# BALPGA.net
KiCad netlist of a schematic drawn in EAGLE
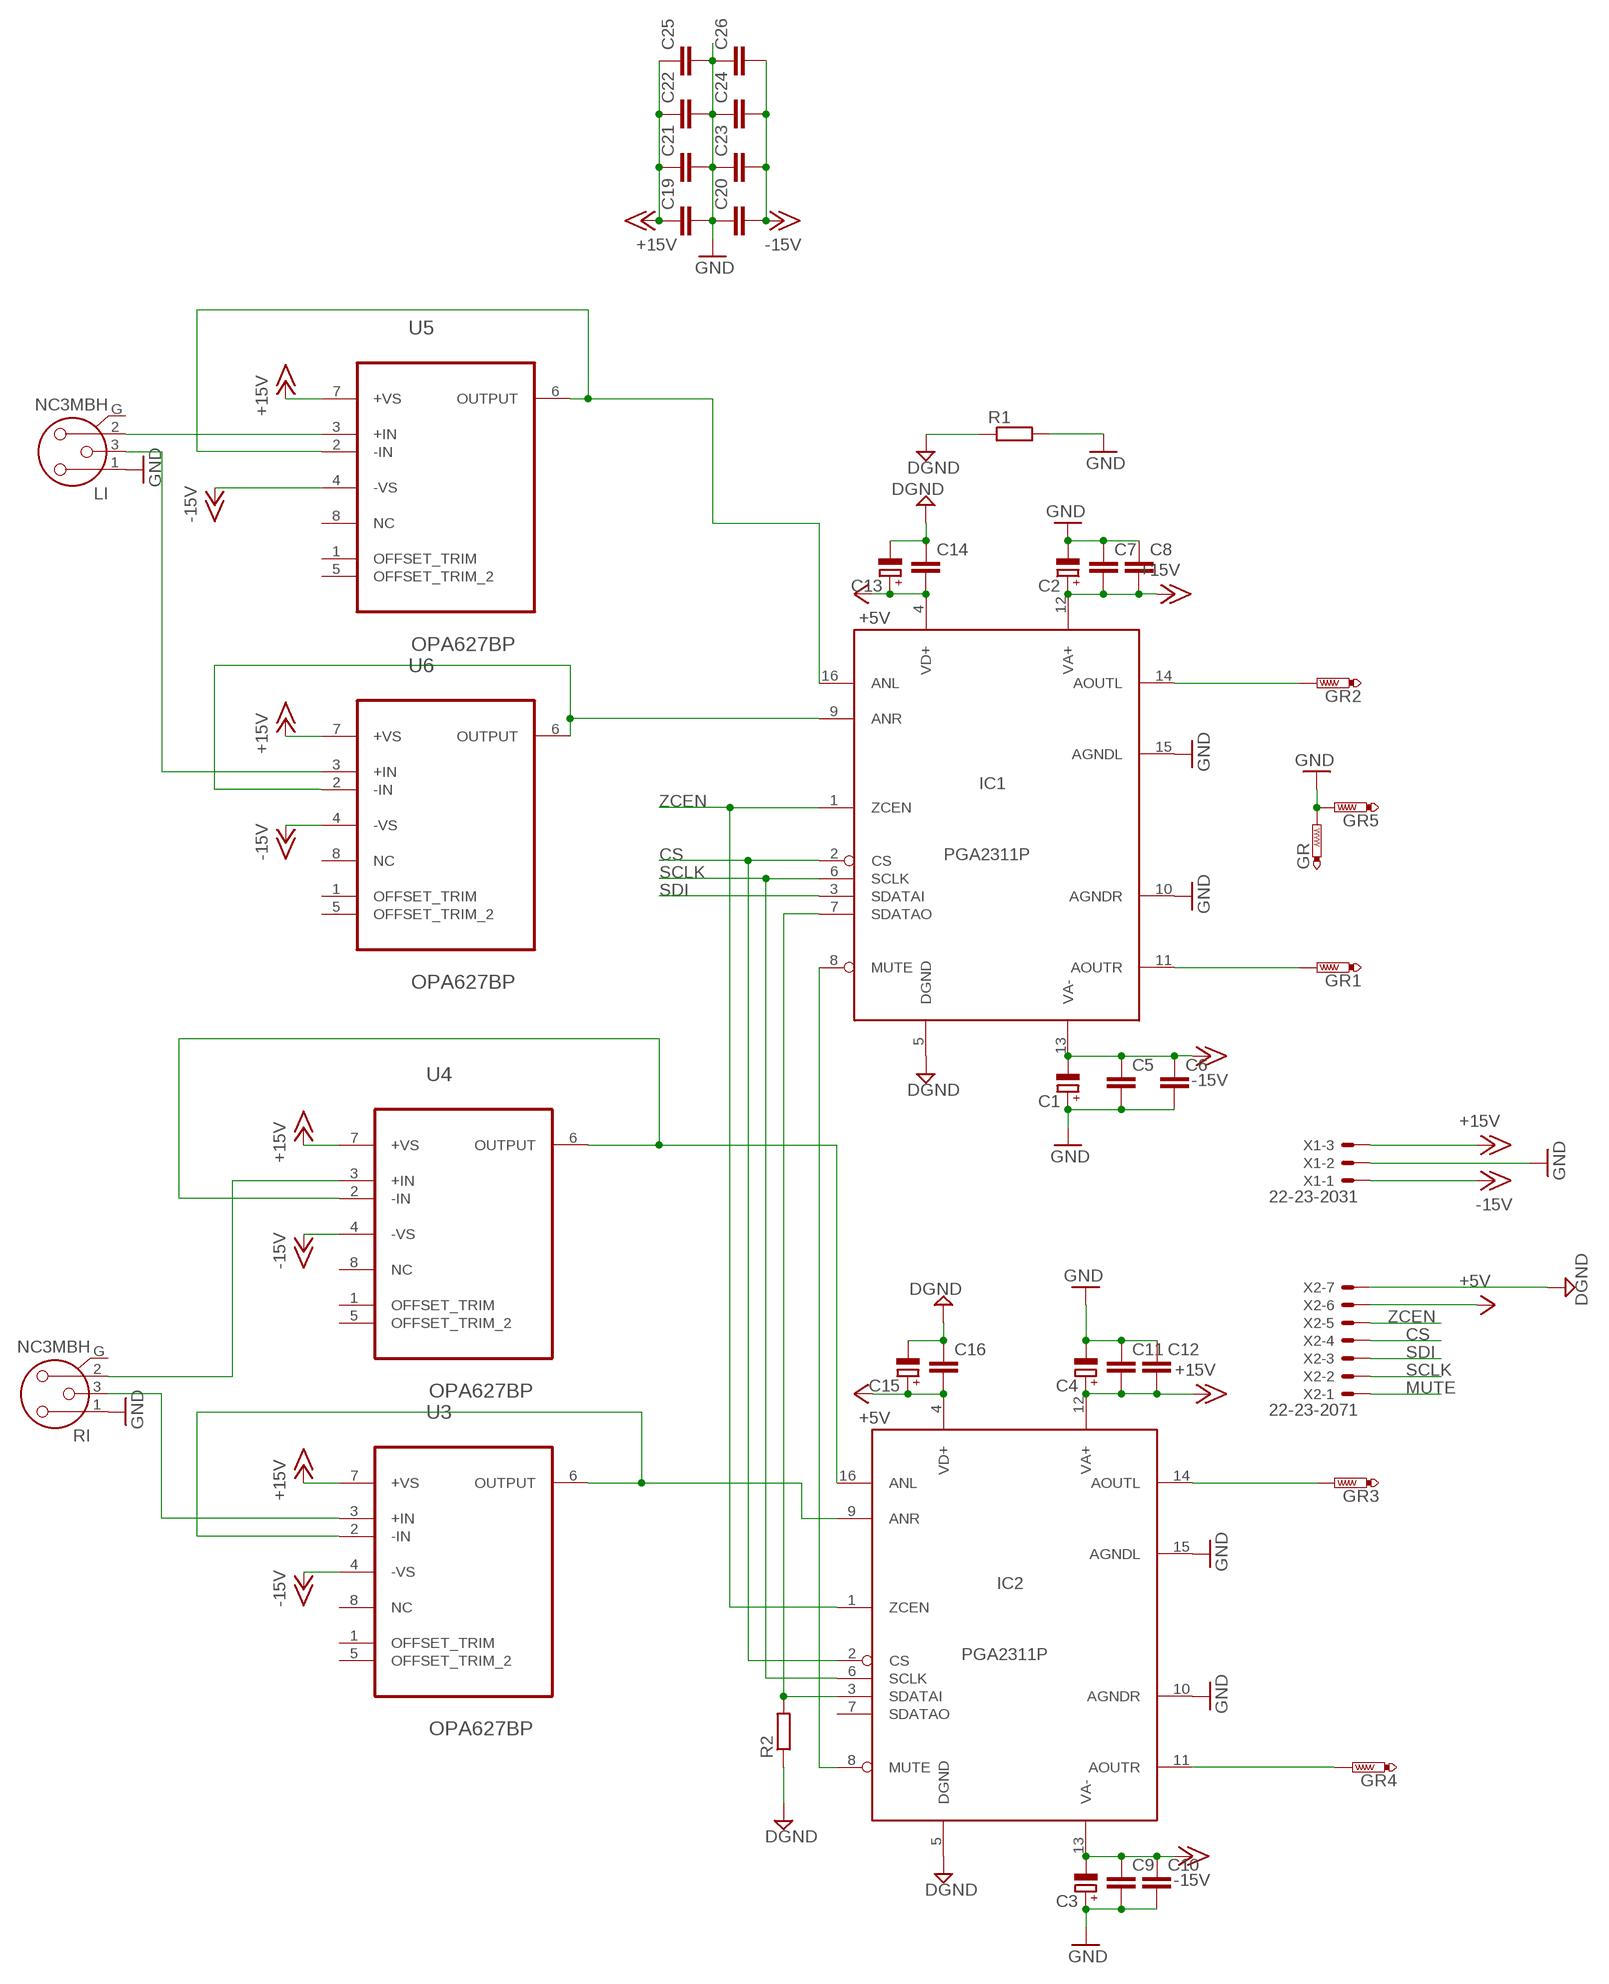
[diagram p0: schematic, sheet 1]

(export (version "E")
  (design (tool "Eeschema 10.0.6"))
  (components
    (comp (ref "C1")
      (value "CPOL-EUSMCD")
      (footprint "eagle-import:SMC_D")
      (libsource (lib "eagle-import") (part "CPOL-EUSMCD"))
    )
    (comp (ref "C2")
      (value "CPOL-EUSMCD")
      (footprint "eagle-import:SMC_D")
      (libsource (lib "eagle-import") (part "CPOL-EUSMCD"))
    )
    (comp (ref "C3")
      (value "CPOL-EUSMCD")
      (footprint "eagle-import:SMC_D")
      (libsource (lib "eagle-import") (part "CPOL-EUSMCD"))
    )
    (comp (ref "C4")
      (value "CPOL-EUSMCD")
      (footprint "eagle-import:SMC_D")
      (libsource (lib "eagle-import") (part "CPOL-EUSMCD"))
    )
    (comp (ref "C5")
      (value "C-EUC1206")
      (footprint "eagle-import:C1206")
      (libsource (lib "eagle-import") (part "C-EUC1206"))
    )
    (comp (ref "C6")
      (value "C-EUC1206")
      (footprint "eagle-import:C1206")
      (libsource (lib "eagle-import") (part "C-EUC1206"))
    )
    (comp (ref "C7")
      (value "C-EUC1206")
      (footprint "eagle-import:C1206")
      (libsource (lib "eagle-import") (part "C-EUC1206"))
    )
    (comp (ref "C8")
      (value "C-EUC1206")
      (footprint "eagle-import:C1206")
      (libsource (lib "eagle-import") (part "C-EUC1206"))
    )
    (comp (ref "C9")
      (value "C-EUC1206")
      (footprint "eagle-import:C1206")
      (libsource (lib "eagle-import") (part "C-EUC1206"))
    )
    (comp (ref "C10")
      (value "C-EUC1206")
      (footprint "eagle-import:C1206")
      (libsource (lib "eagle-import") (part "C-EUC1206"))
    )
    (comp (ref "C11")
      (value "C-EUC1206")
      (footprint "eagle-import:C1206")
      (libsource (lib "eagle-import") (part "C-EUC1206"))
    )
    (comp (ref "C12")
      (value "C-EUC1206")
      (footprint "eagle-import:C1206")
      (libsource (lib "eagle-import") (part "C-EUC1206"))
    )
    (comp (ref "C13")
      (value "CPOL-EUSMCD")
      (footprint "eagle-import:SMC_D")
      (libsource (lib "eagle-import") (part "CPOL-EUSMCD"))
    )
    (comp (ref "C14")
      (value "C-EUC1206")
      (footprint "eagle-import:C1206")
      (libsource (lib "eagle-import") (part "C-EUC1206"))
    )
    (comp (ref "C15")
      (value "CPOL-EUSMCD")
      (footprint "eagle-import:SMC_D")
      (libsource (lib "eagle-import") (part "CPOL-EUSMCD"))
    )
    (comp (ref "C16")
      (value "C-EUC1206")
      (footprint "eagle-import:C1206")
      (libsource (lib "eagle-import") (part "C-EUC1206"))
    )
    (comp (ref "C19")
      (value "C-EUC1206")
      (footprint "eagle-import:C1206")
      (libsource (lib "eagle-import") (part "C-EUC1206"))
    )
    (comp (ref "C20")
      (value "C-EUC1206")
      (footprint "eagle-import:C1206")
      (libsource (lib "eagle-import") (part "C-EUC1206"))
    )
    (comp (ref "C21")
      (value "C-EUC1206")
      (footprint "eagle-import:C1206")
      (libsource (lib "eagle-import") (part "C-EUC1206"))
    )
    (comp (ref "C22")
      (value "C-EUC1206")
      (footprint "eagle-import:C1206")
      (libsource (lib "eagle-import") (part "C-EUC1206"))
    )
    (comp (ref "C23")
      (value "C-EUC1206")
      (footprint "eagle-import:C1206")
      (libsource (lib "eagle-import") (part "C-EUC1206"))
    )
    (comp (ref "C24")
      (value "C-EUC1206")
      (footprint "eagle-import:C1206")
      (libsource (lib "eagle-import") (part "C-EUC1206"))
    )
    (comp (ref "C25")
      (value "C-EUC1206")
      (footprint "eagle-import:C1206")
      (libsource (lib "eagle-import") (part "C-EUC1206"))
    )
    (comp (ref "C26")
      (value "C-EUC1206")
      (footprint "eagle-import:C1206")
      (libsource (lib "eagle-import") (part "C-EUC1206"))
    )
    (comp (ref "GR")
      (value "PTR1PAD1-17")
      (footprint "eagle-import:P1-17")
      (libsource (lib "eagle-import") (part "PTR1PAD1-17"))
    )
    (comp (ref "GR1")
      (value "PTR1PAD1-17")
      (footprint "eagle-import:P1-17")
      (libsource (lib "eagle-import") (part "PTR1PAD1-17"))
    )
    (comp (ref "GR2")
      (value "PTR1PAD1-17")
      (footprint "eagle-import:P1-17")
      (libsource (lib "eagle-import") (part "PTR1PAD1-17"))
    )
    (comp (ref "GR3")
      (value "PTR1PAD1-17")
      (footprint "eagle-import:P1-17")
      (libsource (lib "eagle-import") (part "PTR1PAD1-17"))
    )
    (comp (ref "GR4")
      (value "PTR1PAD1-17")
      (footprint "eagle-import:P1-17")
      (libsource (lib "eagle-import") (part "PTR1PAD1-17"))
    )
    (comp (ref "GR5")
      (value "PTR1PAD1-17")
      (footprint "eagle-import:P1-17")
      (libsource (lib "eagle-import") (part "PTR1PAD1-17"))
    )
    (comp (ref "IC1")
      (value "PGA2311P")
      (footprint "eagle-import:DIL16")
      (libsource (lib "eagle-import") (part "PGA2311P"))
    )
    (comp (ref "IC2")
      (value "PGA2311P")
      (footprint "eagle-import:DIL16")
      (libsource (lib "eagle-import") (part "PGA2311P"))
    )
    (comp (ref "LI")
      (value "NC3MBH")
      (footprint "eagle-import:NC3MBH")
      (fields (field (name "MF") "NEUTRIK"))
      (libsource (lib "eagle-import") (part "NC3MBH"))
    )
    (comp (ref "R1")
      (value "R-EU_0207/10")
      (footprint "eagle-import:0207_10")
      (libsource (lib "eagle-import") (part "resistor_R-EU_0207/10"))
    )
    (comp (ref "R2")
      (value "R-EU_R1206")
      (footprint "eagle-import:R1206")
      (libsource (lib "eagle-import") (part "R-EU_R1206"))
    )
    (comp (ref "RI")
      (value "NC3MBH")
      (footprint "eagle-import:NC3MBH")
      (fields (field (name "MF") "NEUTRIK"))
      (libsource (lib "eagle-import") (part "NC3MBH"))
    )
    (comp (ref "U3")
      (value "OPA627BP")
      (footprint "eagle-import:DIL08")
      (libsource (lib "eagle-import") (part "OPA627BP"))
    )
    (comp (ref "U4")
      (value "OPA627BP")
      (footprint "eagle-import:DIL08")
      (libsource (lib "eagle-import") (part "OPA627BP"))
    )
    (comp (ref "U5")
      (value "OPA627BP")
      (footprint "eagle-import:DIL08")
      (libsource (lib "eagle-import") (part "OPA627BP"))
    )
    (comp (ref "U6")
      (value "OPA627BP")
      (footprint "eagle-import:DIL08")
      (libsource (lib "eagle-import") (part "OPA627BP"))
    )
    (comp (ref "X1")
      (value "22-23-2031")
      (footprint "eagle-import:22-23-2031")
      (fields (field (name "MF") "MOLEX"))
      (libsource (lib "eagle-import") (part "22-23-2031"))
    )
    (comp (ref "X2")
      (value "22-23-2071")
      (footprint "eagle-import:22-23-2071")
      (fields (field (name "MF") "MOLEX"))
      (libsource (lib "eagle-import") (part "22-23-2071"))
    )
  )
  (nets
    (net (code "1") (name "+5V") (class "Default")
      (node (ref "C13") (pin "+") (pinfunction "+_+") (pintype "passive"))
      (node (ref "C14") (pin "2") (pinfunction "2_2") (pintype "passive"))
      (node (ref "C15") (pin "+") (pinfunction "+_+") (pintype "passive"))
      (node (ref "C16") (pin "2") (pinfunction "2_2") (pintype "passive"))
      (node (ref "IC1") (pin "4") (pinfunction "VD+_4") (pintype "power_in"))
      (node (ref "IC2") (pin "4") (pinfunction "VD+_4") (pintype "power_in"))
      (node (ref "X2") (pin "6") (pinfunction "S_6") (pintype "passive"))
    )
    (net (code "2") (name "+15V") (class "Default")
      (node (ref "C11") (pin "2") (pinfunction "2_2") (pintype "passive"))
      (node (ref "C12") (pin "2") (pinfunction "2_2") (pintype "passive"))
      (node (ref "C19") (pin "1") (pinfunction "1_1") (pintype "passive"))
      (node (ref "C2") (pin "+") (pinfunction "+_+") (pintype "passive"))
      (node (ref "C21") (pin "1") (pinfunction "1_1") (pintype "passive"))
      (node (ref "C22") (pin "1") (pinfunction "1_1") (pintype "passive"))
      (node (ref "C25") (pin "1") (pinfunction "1_1") (pintype "passive"))
      (node (ref "C4") (pin "+") (pinfunction "+_+") (pintype "passive"))
      (node (ref "C7") (pin "2") (pinfunction "2_2") (pintype "passive"))
      (node (ref "C8") (pin "2") (pinfunction "2_2") (pintype "passive"))
      (node (ref "IC1") (pin "12") (pinfunction "VA+_12") (pintype "power_in"))
      (node (ref "IC2") (pin "12") (pinfunction "VA+_12") (pintype "power_in"))
      (node (ref "U3") (pin "7") (pinfunction "+VS_7") (pintype "power_in"))
      (node (ref "U4") (pin "7") (pinfunction "+VS_7") (pintype "power_in"))
      (node (ref "U5") (pin "7") (pinfunction "+VS_7") (pintype "power_in"))
      (node (ref "U6") (pin "7") (pinfunction "+VS_7") (pintype "power_in"))
      (node (ref "X1") (pin "3") (pinfunction "S_3") (pintype "passive"))
    )
    (net (code "3") (name "-15V") (class "Default")
      (node (ref "C1") (pin "-") (pinfunction "-_-") (pintype "passive"))
      (node (ref "C10") (pin "1") (pinfunction "1_1") (pintype "passive"))
      (node (ref "C20") (pin "2") (pinfunction "2_2") (pintype "passive"))
      (node (ref "C23") (pin "2") (pinfunction "2_2") (pintype "passive"))
      (node (ref "C24") (pin "2") (pinfunction "2_2") (pintype "passive"))
      (node (ref "C26") (pin "2") (pinfunction "2_2") (pintype "passive"))
      (node (ref "C3") (pin "-") (pinfunction "-_-") (pintype "passive"))
      (node (ref "C5") (pin "1") (pinfunction "1_1") (pintype "passive"))
      (node (ref "C6") (pin "1") (pinfunction "1_1") (pintype "passive"))
      (node (ref "C9") (pin "1") (pinfunction "1_1") (pintype "passive"))
      (node (ref "IC1") (pin "13") (pinfunction "VA-_13") (pintype "power_in"))
      (node (ref "IC2") (pin "13") (pinfunction "VA-_13") (pintype "power_in"))
      (node (ref "U3") (pin "4") (pinfunction "-VS_4") (pintype "power_in"))
      (node (ref "U4") (pin "4") (pinfunction "-VS_4") (pintype "power_in"))
      (node (ref "U5") (pin "4") (pinfunction "-VS_4") (pintype "power_in"))
      (node (ref "U6") (pin "4") (pinfunction "-VS_4") (pintype "power_in"))
      (node (ref "X1") (pin "1") (pinfunction "S_1") (pintype "passive"))
    )
    (net (code "4") (name "/CS") (class "Default")
      (node (ref "IC1") (pin "2") (pinfunction "CS_2") (pintype "input"))
      (node (ref "IC2") (pin "2") (pinfunction "CS_2") (pintype "input"))
      (node (ref "X2") (pin "4") (pinfunction "S_4") (pintype "passive"))
    )
    (net (code "5") (name "/MUTE") (class "Default")
      (node (ref "IC1") (pin "8") (pinfunction "MUTE_8") (pintype "input"))
      (node (ref "IC2") (pin "8") (pinfunction "MUTE_8") (pintype "input"))
      (node (ref "X2") (pin "1") (pinfunction "S_1") (pintype "passive"))
    )
    (net (code "6") (name "/SCLK") (class "Default")
      (node (ref "IC1") (pin "6") (pinfunction "SCLK_6") (pintype "input"))
      (node (ref "IC2") (pin "6") (pinfunction "SCLK_6") (pintype "input"))
      (node (ref "X2") (pin "2") (pinfunction "S_2") (pintype "passive"))
    )
    (net (code "7") (name "/SDI") (class "Default")
      (node (ref "IC1") (pin "3") (pinfunction "SDATAI_3") (pintype "input"))
      (node (ref "X2") (pin "3") (pinfunction "S_3") (pintype "passive"))
    )
    (net (code "8") (name "/ZCEN") (class "Default")
      (node (ref "IC1") (pin "1") (pinfunction "ZCEN_1") (pintype "input"))
      (node (ref "IC2") (pin "1") (pinfunction "ZCEN_1") (pintype "input"))
      (node (ref "X2") (pin "5") (pinfunction "S_5") (pintype "passive"))
    )
    (net (code "9") (name "DGND") (class "Default")
      (node (ref "C13") (pin "-") (pinfunction "-_-") (pintype "passive"))
      (node (ref "C14") (pin "1") (pinfunction "1_1") (pintype "passive"))
      (node (ref "C15") (pin "-") (pinfunction "-_-") (pintype "passive"))
      (node (ref "C16") (pin "1") (pinfunction "1_1") (pintype "passive"))
      (node (ref "IC1") (pin "5") (pinfunction "DGND_5") (pintype "power_in"))
      (node (ref "IC2") (pin "5") (pinfunction "DGND_5") (pintype "power_in"))
      (node (ref "R1") (pin "1") (pinfunction "1_1") (pintype "passive"))
      (node (ref "R2") (pin "1") (pinfunction "1_1") (pintype "passive"))
      (node (ref "X2") (pin "7") (pinfunction "S_7") (pintype "passive"))
    )
    (net (code "10") (name "GND") (class "Default")
      (node (ref "C1") (pin "+") (pinfunction "+_+") (pintype "passive"))
      (node (ref "C10") (pin "2") (pinfunction "2_2") (pintype "passive"))
      (node (ref "C11") (pin "1") (pinfunction "1_1") (pintype "passive"))
      (node (ref "C12") (pin "1") (pinfunction "1_1") (pintype "passive"))
      (node (ref "C19") (pin "2") (pinfunction "2_2") (pintype "passive"))
      (node (ref "C2") (pin "-") (pinfunction "-_-") (pintype "passive"))
      (node (ref "C20") (pin "1") (pinfunction "1_1") (pintype "passive"))
      (node (ref "C21") (pin "2") (pinfunction "2_2") (pintype "passive"))
      (node (ref "C22") (pin "2") (pinfunction "2_2") (pintype "passive"))
      (node (ref "C23") (pin "1") (pinfunction "1_1") (pintype "passive"))
      (node (ref "C24") (pin "1") (pinfunction "1_1") (pintype "passive"))
      (node (ref "C25") (pin "2") (pinfunction "2_2") (pintype "passive"))
      (node (ref "C26") (pin "1") (pinfunction "1_1") (pintype "passive"))
      (node (ref "C3") (pin "+") (pinfunction "+_+") (pintype "passive"))
      (node (ref "C4") (pin "-") (pinfunction "-_-") (pintype "passive"))
      (node (ref "C5") (pin "2") (pinfunction "2_2") (pintype "passive"))
      (node (ref "C6") (pin "2") (pinfunction "2_2") (pintype "passive"))
      (node (ref "C7") (pin "1") (pinfunction "1_1") (pintype "passive"))
      (node (ref "C8") (pin "1") (pinfunction "1_1") (pintype "passive"))
      (node (ref "C9") (pin "2") (pinfunction "2_2") (pintype "passive"))
      (node (ref "GR") (pin "TP") (pinfunction "TP_TP") (pintype "input"))
      (node (ref "GR5") (pin "TP") (pinfunction "TP_TP") (pintype "input"))
      (node (ref "IC1") (pin "10") (pinfunction "AGNDR_10") (pintype "power_in"))
      (node (ref "IC1") (pin "15") (pinfunction "AGNDL_15") (pintype "power_in"))
      (node (ref "IC2") (pin "10") (pinfunction "AGNDR_10") (pintype "power_in"))
      (node (ref "IC2") (pin "15") (pinfunction "AGNDL_15") (pintype "power_in"))
      (node (ref "LI") (pin "1") (pinfunction "1_1") (pintype "passive"))
      (node (ref "R1") (pin "2") (pinfunction "2_2") (pintype "passive"))
      (node (ref "RI") (pin "1") (pinfunction "1_1") (pintype "passive"))
      (node (ref "X1") (pin "2") (pinfunction "S_2") (pintype "passive"))
    )
    (net (code "11") (name "Net-(IC1-ANL)") (class "Default")
      (node (ref "IC1") (pin "16") (pinfunction "ANL_16") (pintype "input"))
      (node (ref "U5") (pin "2") (pinfunction "-IN_2") (pintype "input"))
      (node (ref "U5") (pin "6") (pinfunction "OUTPUT_6") (pintype "output"))
    )
    (net (code "12") (name "Net-(IC1-ANR)") (class "Default")
      (node (ref "IC1") (pin "9") (pinfunction "ANR_9") (pintype "input"))
      (node (ref "U6") (pin "2") (pinfunction "-IN_2") (pintype "input"))
      (node (ref "U6") (pin "6") (pinfunction "OUTPUT_6") (pintype "output"))
    )
    (net (code "13") (name "Net-(IC1-AOUTL)") (class "Default")
      (node (ref "GR2") (pin "TP") (pinfunction "TP_TP") (pintype "input"))
      (node (ref "IC1") (pin "14") (pinfunction "AOUTL_14") (pintype "output"))
    )
    (net (code "14") (name "Net-(IC1-AOUTR)") (class "Default")
      (node (ref "GR1") (pin "TP") (pinfunction "TP_TP") (pintype "input"))
      (node (ref "IC1") (pin "11") (pinfunction "AOUTR_11") (pintype "output"))
    )
    (net (code "15") (name "Net-(IC1-SDATAO)") (class "Default")
      (node (ref "IC1") (pin "7") (pinfunction "SDATAO_7") (pintype "output"))
      (node (ref "IC2") (pin "3") (pinfunction "SDATAI_3") (pintype "input"))
      (node (ref "R2") (pin "2") (pinfunction "2_2") (pintype "passive"))
    )
    (net (code "16") (name "Net-(IC2-ANL)") (class "Default")
      (node (ref "IC2") (pin "16") (pinfunction "ANL_16") (pintype "input"))
      (node (ref "U4") (pin "2") (pinfunction "-IN_2") (pintype "input"))
      (node (ref "U4") (pin "6") (pinfunction "OUTPUT_6") (pintype "output"))
    )
    (net (code "17") (name "Net-(IC2-ANR)") (class "Default")
      (node (ref "IC2") (pin "9") (pinfunction "ANR_9") (pintype "input"))
      (node (ref "U3") (pin "2") (pinfunction "-IN_2") (pintype "input"))
      (node (ref "U3") (pin "6") (pinfunction "OUTPUT_6") (pintype "output"))
    )
    (net (code "18") (name "Net-(IC2-AOUTL)") (class "Default")
      (node (ref "GR3") (pin "TP") (pinfunction "TP_TP") (pintype "input"))
      (node (ref "IC2") (pin "14") (pinfunction "AOUTL_14") (pintype "output"))
    )
    (net (code "19") (name "Net-(IC2-AOUTR)") (class "Default")
      (node (ref "GR4") (pin "TP") (pinfunction "TP_TP") (pintype "input"))
      (node (ref "IC2") (pin "11") (pinfunction "AOUTR_11") (pintype "output"))
    )
    (net (code "20") (name "Net-(U3-+IN)") (class "Default")
      (node (ref "RI") (pin "3") (pinfunction "3_3") (pintype "passive"))
      (node (ref "U3") (pin "3") (pinfunction "+IN_3") (pintype "input"))
    )
    (net (code "21") (name "Net-(U4-+IN)") (class "Default")
      (node (ref "RI") (pin "2") (pinfunction "2_2") (pintype "passive"))
      (node (ref "U4") (pin "3") (pinfunction "+IN_3") (pintype "input"))
    )
    (net (code "22") (name "Net-(U5-+IN)") (class "Default")
      (node (ref "LI") (pin "2") (pinfunction "2_2") (pintype "passive"))
      (node (ref "U5") (pin "3") (pinfunction "+IN_3") (pintype "input"))
    )
    (net (code "23") (name "Net-(U6-+IN)") (class "Default")
      (node (ref "LI") (pin "3") (pinfunction "3_3") (pintype "passive"))
      (node (ref "U6") (pin "3") (pinfunction "+IN_3") (pintype "input"))
    )
    (net (code "24") (name "unconnected-(IC2-SDATAO-Pad7)") (class "Default")
      (node (ref "IC2") (pin "7") (pinfunction "SDATAO_7") (pintype "output"))
    )
    (net (code "25") (name "unconnected-(LI-PadG)") (class "Default")
      (node (ref "LI") (pin "G") (pinfunction "G_G") (pintype "passive"))
    )
    (net (code "26") (name "unconnected-(RI-PadG)") (class "Default")
      (node (ref "RI") (pin "G") (pinfunction "G_G") (pintype "passive"))
    )
    (net (code "27") (name "unconnected-(U3-NC-Pad8)") (class "Default")
      (node (ref "U3") (pin "8") (pinfunction "NC_8") (pintype "no_connect"))
    )
    (net (code "28") (name "unconnected-(U3-OFFSET_TRIM-Pad1)") (class "Default")
      (node (ref "U3") (pin "1") (pinfunction "OFFSET_TRIM_1") (pintype "passive"))
    )
    (net (code "29") (name "unconnected-(U3-OFFSET_TRIM_2-Pad5)") (class "Default")
      (node (ref "U3") (pin "5") (pinfunction "OFFSET_TRIM_2_5") (pintype "passive"))
    )
    (net (code "30") (name "unconnected-(U4-NC-Pad8)") (class "Default")
      (node (ref "U4") (pin "8") (pinfunction "NC_8") (pintype "no_connect"))
    )
    (net (code "31") (name "unconnected-(U4-OFFSET_TRIM-Pad1)") (class "Default")
      (node (ref "U4") (pin "1") (pinfunction "OFFSET_TRIM_1") (pintype "passive"))
    )
    (net (code "32") (name "unconnected-(U4-OFFSET_TRIM_2-Pad5)") (class "Default")
      (node (ref "U4") (pin "5") (pinfunction "OFFSET_TRIM_2_5") (pintype "passive"))
    )
    (net (code "33") (name "unconnected-(U5-NC-Pad8)") (class "Default")
      (node (ref "U5") (pin "8") (pinfunction "NC_8") (pintype "no_connect"))
    )
    (net (code "34") (name "unconnected-(U5-OFFSET_TRIM-Pad1)") (class "Default")
      (node (ref "U5") (pin "1") (pinfunction "OFFSET_TRIM_1") (pintype "passive"))
    )
    (net (code "35") (name "unconnected-(U5-OFFSET_TRIM_2-Pad5)") (class "Default")
      (node (ref "U5") (pin "5") (pinfunction "OFFSET_TRIM_2_5") (pintype "passive"))
    )
    (net (code "36") (name "unconnected-(U6-NC-Pad8)") (class "Default")
      (node (ref "U6") (pin "8") (pinfunction "NC_8") (pintype "no_connect"))
    )
    (net (code "37") (name "unconnected-(U6-OFFSET_TRIM-Pad1)") (class "Default")
      (node (ref "U6") (pin "1") (pinfunction "OFFSET_TRIM_1") (pintype "passive"))
    )
    (net (code "38") (name "unconnected-(U6-OFFSET_TRIM_2-Pad5)") (class "Default")
      (node (ref "U6") (pin "5") (pinfunction "OFFSET_TRIM_2_5") (pintype "passive"))
    )
  )
)
